# TSAL_inv_meas.net
KiCad netlist of a schematic drawn in EAGLE
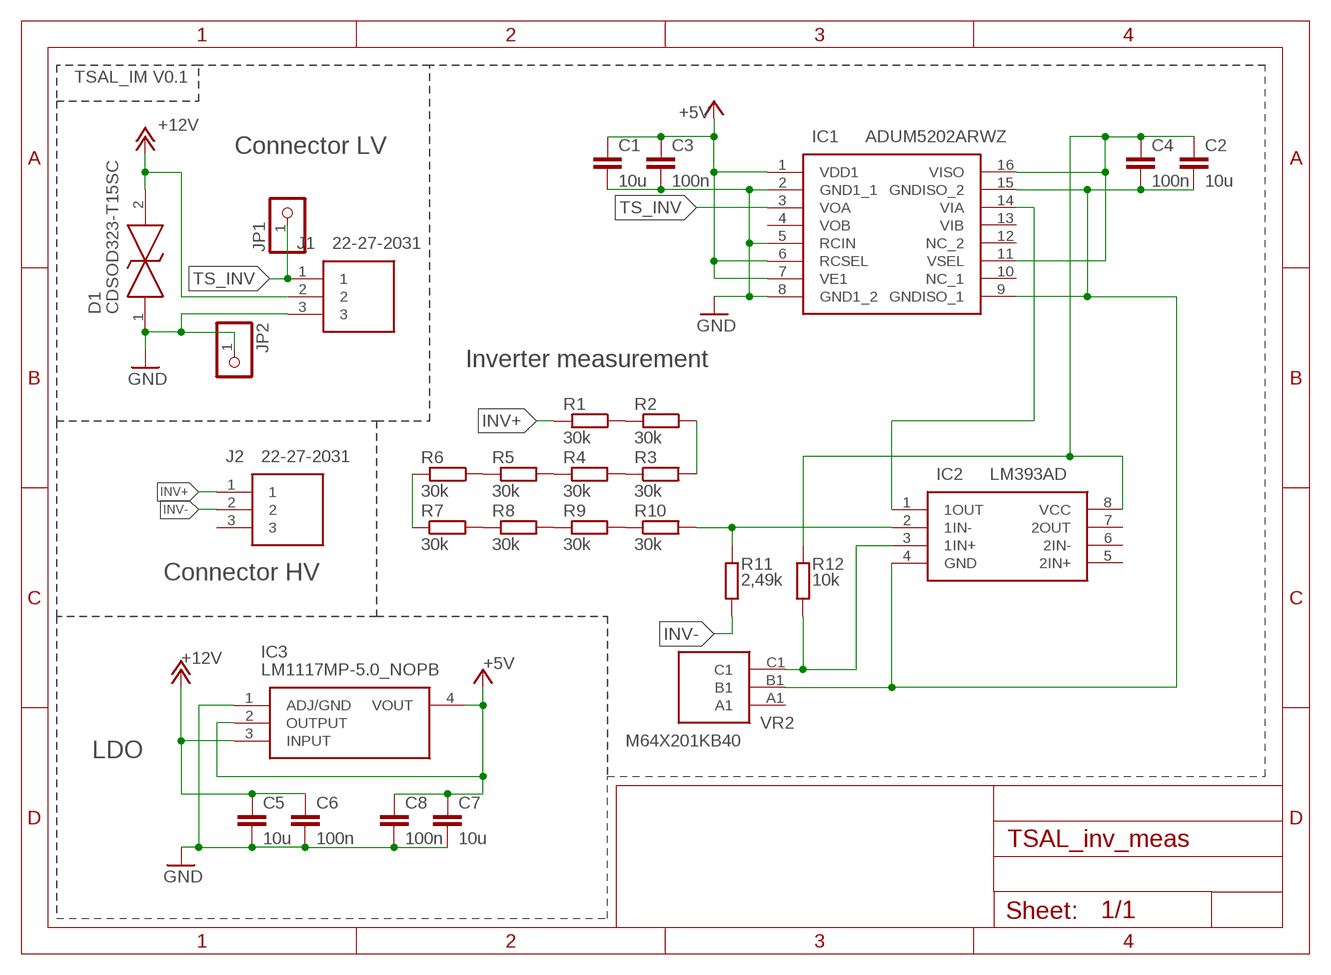
[diagram p0: schematic, sheet 1]

(export (version "E")
  (design (tool "Eeschema 10.0.6"))
  (components
    (comp (ref "C1")
      (value "10u")
      (footprint "eagle-import:C1206")
      (libsource (lib "eagle-import") (part "C-EUC1206"))
    )
    (comp (ref "C2")
      (value "10u")
      (footprint "eagle-import:C1206")
      (libsource (lib "eagle-import") (part "C-EUC1206"))
    )
    (comp (ref "C3")
      (value "100n")
      (footprint "eagle-import:C0603")
      (libsource (lib "eagle-import") (part "C-EUC0603"))
    )
    (comp (ref "C4")
      (value "100n")
      (footprint "eagle-import:C0603")
      (libsource (lib "eagle-import") (part "C-EUC0603"))
    )
    (comp (ref "C5")
      (value "10u")
      (footprint "eagle-import:C1206")
      (libsource (lib "eagle-import") (part "C-EUC1206"))
    )
    (comp (ref "C6")
      (value "100n")
      (footprint "eagle-import:C0603")
      (libsource (lib "eagle-import") (part "C-EUC0603"))
    )
    (comp (ref "C7")
      (value "10u")
      (footprint "eagle-import:C1206")
      (libsource (lib "eagle-import") (part "C-EUC1206"))
    )
    (comp (ref "C8")
      (value "100n")
      (footprint "eagle-import:C0603")
      (libsource (lib "eagle-import") (part "C-EUC0603"))
    )
    (comp (ref "D1")
      (value "CDSOD323-T15SC")
      (footprint "eagle-import:SOD-323")
      (fields (field (name "RS_PART_NUMBER") "7734570"))
      (libsource (lib "eagle-import") (part "CDSOD323-T15SC"))
    )
    (comp (ref "IC1")
      (value "ADUM5202ARWZ")
      (footprint "eagle-import:SOIC127P1032X265-16N")
      (fields (field (name "MOUSER_PART_NUMBER") "584-ADUM5202ARWZ"))
      (libsource (lib "eagle-import") (part "ADUM5202ARWZ"))
    )
    (comp (ref "IC2")
      (value "LM393AD")
      (footprint "eagle-import:SOIC127P600X175-8N")
      (fields (field (name "RS_PART_NUMBER") "5171905P"))
      (libsource (lib "eagle-import") (part "LM393AD"))
    )
    (comp (ref "IC3")
      (value "LM1117MP-5.0_NOPB")
      (footprint "eagle-import:SOT230P700X180-4N")
      (fields
        (field (name "ARROW_PART_NUMBER") "LM1117MP-5.0/NOPB")
        (field (name "MOUSER_PART_NUMBER") "926-LM1117MP-5.0NOPB")
      )
      (libsource (lib "eagle-import") (part "LM1117MP-5.0_NOPB"))
    )
    (comp (ref "J1")
      (value "22-27-2031")
      (footprint "eagle-import:SHDR3W64P0X254_1X3_762X580X111")
      (fields (field (name "RS_PART_NUMBER") "4838477P"))
      (libsource (lib "eagle-import") (part "22-27-2031"))
    )
    (comp (ref "J2")
      (value "22-27-2031")
      (footprint "eagle-import:SHDR3W64P0X254_1X3_762X580X111")
      (fields (field (name "RS_PART_NUMBER") "4838477P"))
      (libsource (lib "eagle-import") (part "22-27-2031"))
    )
    (comp (ref "JP1")
      (value "PINHD-1X1")
      (footprint "eagle-import:1X01")
      (libsource (lib "eagle-import") (part "PINHD-1X1"))
    )
    (comp (ref "JP2")
      (value "PINHD-1X1")
      (footprint "eagle-import:1X01")
      (libsource (lib "eagle-import") (part "PINHD-1X1"))
    )
    (comp (ref "R1")
      (value "30k")
      (footprint "eagle-import:R1206")
      (libsource (lib "eagle-import") (part "R-EU_R1206"))
    )
    (comp (ref "R2")
      (value "30k")
      (footprint "eagle-import:R1206")
      (libsource (lib "eagle-import") (part "R-EU_R1206"))
    )
    (comp (ref "R3")
      (value "30k")
      (footprint "eagle-import:R1206")
      (libsource (lib "eagle-import") (part "R-EU_R1206"))
    )
    (comp (ref "R4")
      (value "30k")
      (footprint "eagle-import:R1206")
      (libsource (lib "eagle-import") (part "R-EU_R1206"))
    )
    (comp (ref "R5")
      (value "30k")
      (footprint "eagle-import:R1206")
      (libsource (lib "eagle-import") (part "R-EU_R1206"))
    )
    (comp (ref "R6")
      (value "30k")
      (footprint "eagle-import:R1206")
      (libsource (lib "eagle-import") (part "R-EU_R1206"))
    )
    (comp (ref "R7")
      (value "30k")
      (footprint "eagle-import:R1206")
      (libsource (lib "eagle-import") (part "R-EU_R1206"))
    )
    (comp (ref "R8")
      (value "30k")
      (footprint "eagle-import:R1206")
      (libsource (lib "eagle-import") (part "R-EU_R1206"))
    )
    (comp (ref "R9")
      (value "30k")
      (footprint "eagle-import:R1206")
      (libsource (lib "eagle-import") (part "R-EU_R1206"))
    )
    (comp (ref "R10")
      (value "30k")
      (footprint "eagle-import:R1206")
      (libsource (lib "eagle-import") (part "R-EU_R1206"))
    )
    (comp (ref "R11")
      (value "2,49k")
      (footprint "eagle-import:R0603")
      (libsource (lib "eagle-import") (part "R-EU_R0603"))
    )
    (comp (ref "R12")
      (value "10k")
      (footprint "eagle-import:R0603")
      (libsource (lib "eagle-import") (part "R-EU_R0603"))
    )
    (comp (ref "VR2")
      (value "M64X201KB40")
      (footprint "eagle-import:M64X201KB40")
      (fields (field (name "MOUSER_PART_NUMBER") "594-64X201"))
      (libsource (lib "eagle-import") (part "M64X201KB40"))
    )
  )
  (nets
    (net (code "1") (name "+5V") (class "Default")
      (node (ref "C1") (pin "1") (pinfunction "1_1") (pintype "passive"))
      (node (ref "C3") (pin "1") (pinfunction "1_1") (pintype "passive"))
      (node (ref "C7") (pin "1") (pinfunction "1_1") (pintype "passive"))
      (node (ref "C8") (pin "1") (pinfunction "1_1") (pintype "passive"))
      (node (ref "IC1") (pin "1") (pinfunction "VDD1_1") (pintype "power_in"))
      (node (ref "IC1") (pin "6") (pinfunction "RCSEL_6") (pintype "input"))
      (node (ref "IC1") (pin "7") (pinfunction "VE1_7") (pintype "bidirectional"))
      (node (ref "IC3") (pin "2") (pinfunction "OUTPUT_2") (pintype "bidirectional"))
      (node (ref "IC3") (pin "4") (pinfunction "VOUT_4") (pintype "bidirectional"))
    )
    (net (code "2") (name "+12V") (class "Default")
      (node (ref "C5") (pin "1") (pinfunction "1_1") (pintype "passive"))
      (node (ref "C6") (pin "1") (pinfunction "1_1") (pintype "passive"))
      (node (ref "D1") (pin "2") (pinfunction "2_2") (pintype "bidirectional"))
      (node (ref "IC3") (pin "3") (pinfunction "INPUT_3") (pintype "bidirectional"))
      (node (ref "J1") (pin "2") (pinfunction "2_2") (pintype "bidirectional"))
    )
    (net (code "3") (name "GND") (class "Default")
      (node (ref "C1") (pin "2") (pinfunction "2_2") (pintype "passive"))
      (node (ref "C3") (pin "2") (pinfunction "2_2") (pintype "passive"))
      (node (ref "C5") (pin "2") (pinfunction "2_2") (pintype "passive"))
      (node (ref "C6") (pin "2") (pinfunction "2_2") (pintype "passive"))
      (node (ref "C7") (pin "2") (pinfunction "2_2") (pintype "passive"))
      (node (ref "C8") (pin "2") (pinfunction "2_2") (pintype "passive"))
      (node (ref "D1") (pin "1") (pinfunction "1_1") (pintype "bidirectional"))
      (node (ref "IC1") (pin "2") (pinfunction "GND1_1_2") (pintype "power_in"))
      (node (ref "IC1") (pin "5") (pinfunction "RCIN_5") (pintype "input"))
      (node (ref "IC1") (pin "8") (pinfunction "GND1_2_8") (pintype "power_in"))
      (node (ref "IC3") (pin "1") (pinfunction "ADJ/GND_1") (pintype "bidirectional"))
      (node (ref "J1") (pin "3") (pinfunction "3_3") (pintype "bidirectional"))
      (node (ref "JP2") (pin "1") (pinfunction "1_1") (pintype "passive"))
    )
    (net (code "4") (name "INV+") (class "Default")
      (node (ref "J2") (pin "1") (pinfunction "1_1") (pintype "bidirectional"))
      (node (ref "R1") (pin "2") (pinfunction "2_2") (pintype "passive"))
    )
    (net (code "5") (name "INV-") (class "Default")
      (node (ref "J2") (pin "2") (pinfunction "2_2") (pintype "bidirectional"))
      (node (ref "R11") (pin "2") (pinfunction "2_2") (pintype "passive"))
    )
    (net (code "6") (name "Net-(IC1-GNDISO_1)") (class "Default")
      (node (ref "C2") (pin "2") (pinfunction "2_2") (pintype "passive"))
      (node (ref "C4") (pin "2") (pinfunction "2_2") (pintype "passive"))
      (node (ref "IC1") (pin "15") (pinfunction "GNDISO_2_15") (pintype "power_in"))
      (node (ref "IC1") (pin "9") (pinfunction "GNDISO_1_9") (pintype "power_in"))
      (node (ref "IC2") (pin "4") (pinfunction "GND_4") (pintype "bidirectional"))
      (node (ref "VR2") (pin "B1") (pinfunction "B1_B1") (pintype "bidirectional"))
    )
    (net (code "7") (name "Net-(IC1-VIA)") (class "Default")
      (node (ref "IC1") (pin "14") (pinfunction "VIA_14") (pintype "bidirectional"))
      (node (ref "IC2") (pin "1") (pinfunction "1OUT_1") (pintype "bidirectional"))
    )
    (net (code "8") (name "Net-(IC1-VISO)") (class "Default")
      (node (ref "C2") (pin "1") (pinfunction "1_1") (pintype "passive"))
      (node (ref "C4") (pin "1") (pinfunction "1_1") (pintype "passive"))
      (node (ref "IC1") (pin "11") (pinfunction "VSEL_11") (pintype "bidirectional"))
      (node (ref "IC1") (pin "16") (pinfunction "VISO_16") (pintype "bidirectional"))
      (node (ref "IC2") (pin "8") (pinfunction "VCC_8") (pintype "bidirectional"))
      (node (ref "R12") (pin "1") (pinfunction "1_1") (pintype "passive"))
    )
    (net (code "9") (name "Net-(IC2-1IN+)") (class "Default")
      (node (ref "IC2") (pin "3") (pinfunction "1IN+_3") (pintype "bidirectional"))
      (node (ref "R12") (pin "2") (pinfunction "2_2") (pintype "passive"))
      (node (ref "VR2") (pin "C1") (pinfunction "C1_C1") (pintype "bidirectional"))
    )
    (net (code "10") (name "Net-(IC2-1IN-)") (class "Default")
      (node (ref "IC2") (pin "2") (pinfunction "1IN-_2") (pintype "bidirectional"))
      (node (ref "R10") (pin "2") (pinfunction "2_2") (pintype "passive"))
      (node (ref "R11") (pin "1") (pinfunction "1_1") (pintype "passive"))
    )
    (net (code "11") (name "Net-(R1-Pad1)") (class "Default")
      (node (ref "R1") (pin "1") (pinfunction "1_1") (pintype "passive"))
      (node (ref "R2") (pin "2") (pinfunction "2_2") (pintype "passive"))
    )
    (net (code "12") (name "Net-(R2-Pad1)") (class "Default")
      (node (ref "R2") (pin "1") (pinfunction "1_1") (pintype "passive"))
      (node (ref "R3") (pin "2") (pinfunction "2_2") (pintype "passive"))
    )
    (net (code "13") (name "Net-(R3-Pad1)") (class "Default")
      (node (ref "R3") (pin "1") (pinfunction "1_1") (pintype "passive"))
      (node (ref "R4") (pin "2") (pinfunction "2_2") (pintype "passive"))
    )
    (net (code "14") (name "Net-(R4-Pad1)") (class "Default")
      (node (ref "R4") (pin "1") (pinfunction "1_1") (pintype "passive"))
      (node (ref "R5") (pin "2") (pinfunction "2_2") (pintype "passive"))
    )
    (net (code "15") (name "Net-(R5-Pad1)") (class "Default")
      (node (ref "R5") (pin "1") (pinfunction "1_1") (pintype "passive"))
      (node (ref "R6") (pin "1") (pinfunction "1_1") (pintype "passive"))
    )
    (net (code "16") (name "Net-(R6-Pad2)") (class "Default")
      (node (ref "R6") (pin "2") (pinfunction "2_2") (pintype "passive"))
      (node (ref "R7") (pin "1") (pinfunction "1_1") (pintype "passive"))
    )
    (net (code "17") (name "Net-(R7-Pad2)") (class "Default")
      (node (ref "R7") (pin "2") (pinfunction "2_2") (pintype "passive"))
      (node (ref "R8") (pin "1") (pinfunction "1_1") (pintype "passive"))
    )
    (net (code "18") (name "Net-(R8-Pad2)") (class "Default")
      (node (ref "R8") (pin "2") (pinfunction "2_2") (pintype "passive"))
      (node (ref "R9") (pin "1") (pinfunction "1_1") (pintype "passive"))
    )
    (net (code "19") (name "Net-(R10-Pad1)") (class "Default")
      (node (ref "R10") (pin "1") (pinfunction "1_1") (pintype "passive"))
      (node (ref "R9") (pin "2") (pinfunction "2_2") (pintype "passive"))
    )
    (net (code "20") (name "TS_INV") (class "Default")
      (node (ref "IC1") (pin "3") (pinfunction "VOA_3") (pintype "bidirectional"))
      (node (ref "J1") (pin "1") (pinfunction "1_1") (pintype "bidirectional"))
      (node (ref "JP1") (pin "1") (pinfunction "1_1") (pintype "passive"))
    )
    (net (code "21") (name "unconnected-(IC1-NC_1-Pad10)") (class "Default")
      (node (ref "IC1") (pin "10") (pinfunction "NC_1_10") (pintype "bidirectional"))
    )
    (net (code "22") (name "unconnected-(IC1-NC_2-Pad12)") (class "Default")
      (node (ref "IC1") (pin "12") (pinfunction "NC_2_12") (pintype "bidirectional"))
    )
    (net (code "23") (name "unconnected-(IC1-VIB-Pad13)") (class "Default")
      (node (ref "IC1") (pin "13") (pinfunction "VIB_13") (pintype "bidirectional"))
    )
    (net (code "24") (name "unconnected-(IC1-VOB-Pad4)") (class "Default")
      (node (ref "IC1") (pin "4") (pinfunction "VOB_4") (pintype "bidirectional"))
    )
    (net (code "25") (name "unconnected-(IC2-2IN+-Pad5)") (class "Default")
      (node (ref "IC2") (pin "5") (pinfunction "2IN+_5") (pintype "bidirectional"))
    )
    (net (code "26") (name "unconnected-(IC2-2IN--Pad6)") (class "Default")
      (node (ref "IC2") (pin "6") (pinfunction "2IN-_6") (pintype "bidirectional"))
    )
    (net (code "27") (name "unconnected-(IC2-2OUT-Pad7)") (class "Default")
      (node (ref "IC2") (pin "7") (pinfunction "2OUT_7") (pintype "bidirectional"))
    )
    (net (code "28") (name "unconnected-(J2-Pad3)") (class "Default")
      (node (ref "J2") (pin "3") (pinfunction "3_3") (pintype "bidirectional"))
    )
    (net (code "29") (name "unconnected-(VR2-PadA1)") (class "Default")
      (node (ref "VR2") (pin "A1") (pinfunction "A1_A1") (pintype "bidirectional"))
    )
  )
)
